# bolid-mcu.net
KiCad netlist of a schematic drawn in Altium Designer
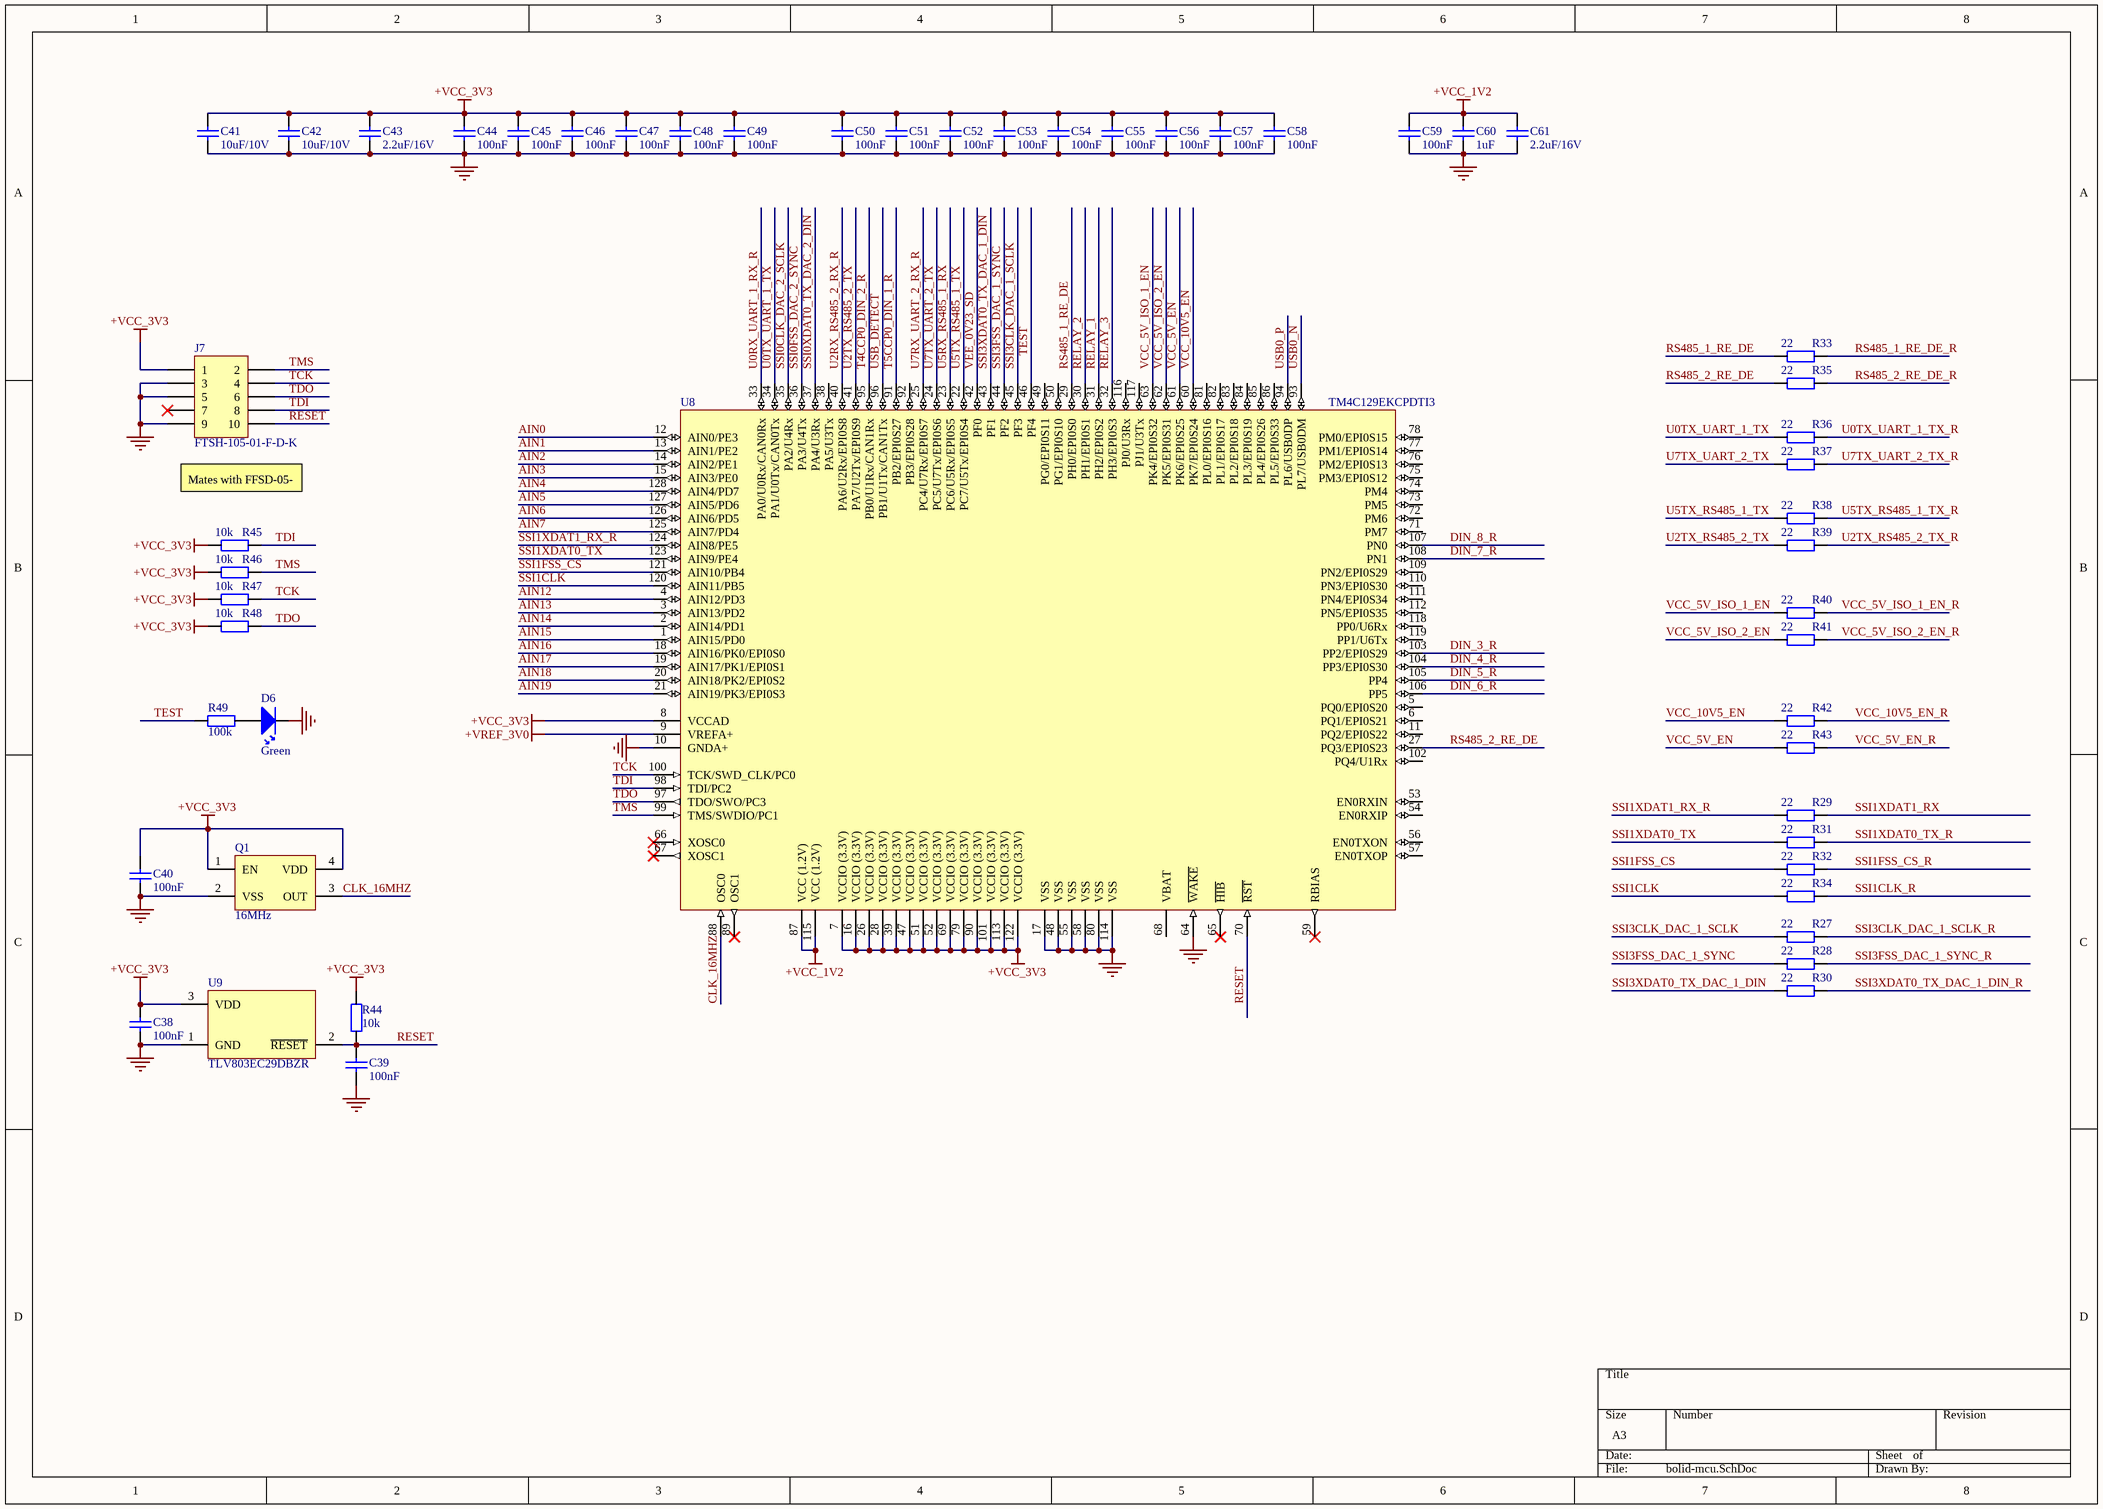
[diagram p0: bolid-mcu.SchDoc]

(export (version "E")
  (design (tool "Eeschema 10.0.6"))
  (components
    (comp (ref "C38")
      (value "GRM155R71H104KE14D")
      (footprint "C0402-CAPC100X50X55L22 - Tayio Yuden TDK")
      (description "MLCC 0402 (1005) 100nF 10% 50V X7R")
      (fields
        (field (name "MANUFACTURER") "Murata Electronics")
        (field (name "TOLERANCE") "10 %")
        (field (name "VALUE DISPLAYED") "100nF")
      )
      (libsource (lib "capacitors2") (part "GRM155R71H104KE14D"))
    )
    (comp (ref "C39")
      (value "GRM155R71H104KE14D")
      (footprint "C0402-CAPC100X50X55L22 - Tayio Yuden TDK")
      (description "MLCC 0402 (1005) 100nF 10% 50V X7R")
      (fields
        (field (name "MANUFACTURER") "Murata Electronics")
        (field (name "TOLERANCE") "10 %")
        (field (name "VALUE DISPLAYED") "100nF")
      )
      (libsource (lib "capacitors2") (part "GRM155R71H104KE14D"))
    )
    (comp (ref "C40")
      (value "GRM155R71H104KE14D")
      (footprint "C0402-CAPC100X50X55L22 - Tayio Yuden TDK")
      (description "MLCC 0402 (1005) 100nF 10% 50V X7R")
      (fields
        (field (name "MANUFACTURER") "Murata Electronics")
        (field (name "TOLERANCE") "10 %")
        (field (name "VALUE DISPLAYED") "100nF")
      )
      (libsource (lib "capacitors2") (part "GRM155R71H104KE14D"))
    )
    (comp (ref "C41")
      (value "GRM21BR71A106KA73K")
      (footprint "C0805-CAPC200X125X135L50N - Taiyo YudenN")
      (description "MLCC 0805 (2012) 10uF 10% 10V X7R")
      (fields
        (field (name "MANUFACTURER") "Murata Electronics")
        (field (name "TOLERANCE") "10 %")
        (field (name "VALUE DISPLAYED") "10uF/10V")
      )
      (libsource (lib "capacitors2") (part "GRM21BR71A106KA73K"))
    )
    (comp (ref "C42")
      (value "GRM21BR71A106KA73K")
      (footprint "C0805-CAPC200X125X135L50N - Taiyo YudenN")
      (description "MLCC 0805 (2012) 10uF 10% 10V X7R")
      (fields
        (field (name "MANUFACTURER") "Murata Electronics")
        (field (name "TOLERANCE") "10 %")
        (field (name "VALUE DISPLAYED") "10uF/10V")
      )
      (libsource (lib "capacitors2") (part "GRM21BR71A106KA73K"))
    )
    (comp (ref "C43")
      (value "EMK107BB7225MA-T")
      (footprint "C0603-CAPC162X80X95L35N")
      (description "MLCC 0603 (1608) 2.2uF 20% 16V X7R")
      (fields
        (field (name "MANUFACTURER") "Taiyo Yuden")
        (field (name "TOLERANCE") "20 %")
        (field (name "VALUE DISPLAYED") "2.2uF/16V")
      )
      (libsource (lib "capacitors2") (part "EMK107BB7225MA-T"))
    )
    (comp (ref "C44")
      (value "GRM155R71H104KE14D")
      (footprint "C0402-CAPC100X50X55L22 - Tayio Yuden TDK")
      (description "MLCC 0402 (1005) 100nF 10% 50V X7R")
      (fields
        (field (name "MANUFACTURER") "Murata Electronics")
        (field (name "TOLERANCE") "10 %")
        (field (name "VALUE DISPLAYED") "100nF")
      )
      (libsource (lib "capacitors2") (part "GRM155R71H104KE14D"))
    )
    (comp (ref "C45")
      (value "GRM155R71H104KE14D")
      (footprint "C0402-CAPC100X50X55L22 - Tayio Yuden TDK")
      (description "MLCC 0402 (1005) 100nF 10% 50V X7R")
      (fields
        (field (name "MANUFACTURER") "Murata Electronics")
        (field (name "TOLERANCE") "10 %")
        (field (name "VALUE DISPLAYED") "100nF")
      )
      (libsource (lib "capacitors2") (part "GRM155R71H104KE14D"))
    )
    (comp (ref "C46")
      (value "GRM155R71H104KE14D")
      (footprint "C0402-CAPC100X50X55L22 - Tayio Yuden TDK")
      (description "MLCC 0402 (1005) 100nF 10% 50V X7R")
      (fields
        (field (name "MANUFACTURER") "Murata Electronics")
        (field (name "TOLERANCE") "10 %")
        (field (name "VALUE DISPLAYED") "100nF")
      )
      (libsource (lib "capacitors2") (part "GRM155R71H104KE14D"))
    )
    (comp (ref "C47")
      (value "GRM155R71H104KE14D")
      (footprint "C0402-CAPC100X50X55L22 - Tayio Yuden TDK")
      (description "MLCC 0402 (1005) 100nF 10% 50V X7R")
      (fields
        (field (name "MANUFACTURER") "Murata Electronics")
        (field (name "TOLERANCE") "10 %")
        (field (name "VALUE DISPLAYED") "100nF")
      )
      (libsource (lib "capacitors2") (part "GRM155R71H104KE14D"))
    )
    (comp (ref "C48")
      (value "GRM155R71H104KE14D")
      (footprint "C0402-CAPC100X50X55L22 - Tayio Yuden TDK")
      (description "MLCC 0402 (1005) 100nF 10% 50V X7R")
      (fields
        (field (name "MANUFACTURER") "Murata Electronics")
        (field (name "TOLERANCE") "10 %")
        (field (name "VALUE DISPLAYED") "100nF")
      )
      (libsource (lib "capacitors2") (part "GRM155R71H104KE14D"))
    )
    (comp (ref "C49")
      (value "GRM155R71H104KE14D")
      (footprint "C0402-CAPC100X50X55L22 - Tayio Yuden TDK")
      (description "MLCC 0402 (1005) 100nF 10% 50V X7R")
      (fields
        (field (name "MANUFACTURER") "Murata Electronics")
        (field (name "TOLERANCE") "10 %")
        (field (name "VALUE DISPLAYED") "100nF")
      )
      (libsource (lib "capacitors2") (part "GRM155R71H104KE14D"))
    )
    (comp (ref "C50")
      (value "GRM155R71H104KE14D")
      (footprint "C0402-CAPC100X50X55L22 - Tayio Yuden TDK")
      (description "MLCC 0402 (1005) 100nF 10% 50V X7R")
      (fields
        (field (name "MANUFACTURER") "Murata Electronics")
        (field (name "TOLERANCE") "10 %")
        (field (name "VALUE DISPLAYED") "100nF")
      )
      (libsource (lib "capacitors2") (part "GRM155R71H104KE14D"))
    )
    (comp (ref "C51")
      (value "GRM155R71H104KE14D")
      (footprint "C0402-CAPC100X50X55L22 - Tayio Yuden TDK")
      (description "MLCC 0402 (1005) 100nF 10% 50V X7R")
      (fields
        (field (name "MANUFACTURER") "Murata Electronics")
        (field (name "TOLERANCE") "10 %")
        (field (name "VALUE DISPLAYED") "100nF")
      )
      (libsource (lib "capacitors2") (part "GRM155R71H104KE14D"))
    )
    (comp (ref "C52")
      (value "GRM155R71H104KE14D")
      (footprint "C0402-CAPC100X50X55L22 - Tayio Yuden TDK")
      (description "MLCC 0402 (1005) 100nF 10% 50V X7R")
      (fields
        (field (name "MANUFACTURER") "Murata Electronics")
        (field (name "TOLERANCE") "10 %")
        (field (name "VALUE DISPLAYED") "100nF")
      )
      (libsource (lib "capacitors2") (part "GRM155R71H104KE14D"))
    )
    (comp (ref "C53")
      (value "GRM155R71H104KE14D")
      (footprint "C0402-CAPC100X50X55L22 - Tayio Yuden TDK")
      (description "MLCC 0402 (1005) 100nF 10% 50V X7R")
      (fields
        (field (name "MANUFACTURER") "Murata Electronics")
        (field (name "TOLERANCE") "10 %")
        (field (name "VALUE DISPLAYED") "100nF")
      )
      (libsource (lib "capacitors2") (part "GRM155R71H104KE14D"))
    )
    (comp (ref "C54")
      (value "GRM155R71H104KE14D")
      (footprint "C0402-CAPC100X50X55L22 - Tayio Yuden TDK")
      (description "MLCC 0402 (1005) 100nF 10% 50V X7R")
      (fields
        (field (name "MANUFACTURER") "Murata Electronics")
        (field (name "TOLERANCE") "10 %")
        (field (name "VALUE DISPLAYED") "100nF")
      )
      (libsource (lib "capacitors2") (part "GRM155R71H104KE14D"))
    )
    (comp (ref "C55")
      (value "GRM155R71H104KE14D")
      (footprint "C0402-CAPC100X50X55L22 - Tayio Yuden TDK")
      (description "MLCC 0402 (1005) 100nF 10% 50V X7R")
      (fields
        (field (name "MANUFACTURER") "Murata Electronics")
        (field (name "TOLERANCE") "10 %")
        (field (name "VALUE DISPLAYED") "100nF")
      )
      (libsource (lib "capacitors2") (part "GRM155R71H104KE14D"))
    )
    (comp (ref "C56")
      (value "GRM155R71H104KE14D")
      (footprint "C0402-CAPC100X50X55L22 - Tayio Yuden TDK")
      (description "MLCC 0402 (1005) 100nF 10% 50V X7R")
      (fields
        (field (name "MANUFACTURER") "Murata Electronics")
        (field (name "TOLERANCE") "10 %")
        (field (name "VALUE DISPLAYED") "100nF")
      )
      (libsource (lib "capacitors2") (part "GRM155R71H104KE14D"))
    )
    (comp (ref "C57")
      (value "GRM155R71H104KE14D")
      (footprint "C0402-CAPC100X50X55L22 - Tayio Yuden TDK")
      (description "MLCC 0402 (1005) 100nF 10% 50V X7R")
      (fields
        (field (name "MANUFACTURER") "Murata Electronics")
        (field (name "TOLERANCE") "10 %")
        (field (name "VALUE DISPLAYED") "100nF")
      )
      (libsource (lib "capacitors2") (part "GRM155R71H104KE14D"))
    )
    (comp (ref "C58")
      (value "GRM155R71H104KE14D")
      (footprint "C0402-CAPC100X50X55L22 - Tayio Yuden TDK")
      (description "MLCC 0402 (1005) 100nF 10% 50V X7R")
      (fields
        (field (name "MANUFACTURER") "Murata Electronics")
        (field (name "TOLERANCE") "10 %")
        (field (name "VALUE DISPLAYED") "100nF")
      )
      (libsource (lib "capacitors2") (part "GRM155R71H104KE14D"))
    )
    (comp (ref "C59")
      (value "GRM155R71H104KE14D")
      (footprint "C0402-CAPC100X50X55L22 - Tayio Yuden TDK")
      (description "MLCC 0402 (1005) 100nF 10% 50V X7R")
      (fields
        (field (name "MANUFACTURER") "Murata Electronics")
        (field (name "TOLERANCE") "10 %")
        (field (name "VALUE DISPLAYED") "100nF")
      )
      (libsource (lib "capacitors2") (part "GRM155R71H104KE14D"))
    )
    (comp (ref "C60")
      (value "UMK107AB7105KA-T")
      (footprint "C0603-CAPC162X80X95L35N")
      (description "MLCC 0603 (1608) 1uF 10% 50V X7R")
      (fields
        (field (name "MANUFACTURER") "Taiyo Yuden")
        (field (name "TOLERANCE") "10 %")
        (field (name "VALUE DISPLAYED") "1uF")
      )
      (libsource (lib "capacitors2") (part "UMK107AB7105KA-T"))
    )
    (comp (ref "C61")
      (value "EMK107BB7225MA-T")
      (footprint "C0603-CAPC162X80X95L35N")
      (description "MLCC 0603 (1608) 2.2uF 20% 16V X7R")
      (fields
        (field (name "MANUFACTURER") "Taiyo Yuden")
        (field (name "TOLERANCE") "20 %")
        (field (name "VALUE DISPLAYED") "2.2uF/16V")
      )
      (libsource (lib "capacitors2") (part "EMK107BB7225MA-T"))
    )
    (comp (ref "D6")
      (value "150060GS75000")
      (footprint "D0603 DIONC166X84X36L42N Littelfuse")
      (description "LED 0603 (1608) Green")
      (fields (field (name "MANUFACTURER") "Wurth Elektronik") (field (name "ILLUMINATION COLOR") "Green"))
      (libsource (lib "semiconductors2") (part "150060GS75000"))
    )
    (comp (ref "J7")
      (value "FTSH-105-01-F-D-K")
      (footprint "SAMTEC-FTSH-105-01-F-D-K")
      (description "Conn Unshrouded Header HDR 10 POS 1.27mm Solder ST Top Entry Thru-Hole Tube")
      (fields (field (name "MANUFACTURER") "Samtec"))
      (libsource (lib "connectors2") (part "FTSH-105-01-F-D-K"))
    )
    (comp (ref "Q1")
      (value "16MHz")
      (footprint "ECS ECS-2520S OSCCC250X200X100L67X77")
      (description "Oscillator XO 16MHz ±25ppm 15pF CMOS 55% 1.8V/2.5V/3.3V 4-Pin Mini-CSMD T/R")
      (fields
        (field (name "MANUFACTURER") "ECS International")
        (field (name "MANUFACTURER PART NUMBER") "ECS-2520MVLC-160-CN-TR")
      )
      (libsource (lib "misc2") (part "ECS-2520MVLC-160-CN-TR"))
    )
    (comp (ref "R27")
      (value "22")
      (footprint "R0402-RESC100X50X40L22N")
      (description "RES 0402 (1005) 22.0 ohm 1% 0.0625W 50V Thick Film")
      (fields
        (field (name "MANUFACTURER") "Yageo")
        (field (name "MANUFACTURER PART NUMBER") "RC0402FR-1322RL")
      )
      (libsource (lib "resistors2") (part "RC0402FR-1322RL"))
    )
    (comp (ref "R28")
      (value "22")
      (footprint "R0402-RESC100X50X40L22N")
      (description "RES 0402 (1005) 22.0 ohm 1% 0.0625W 50V Thick Film")
      (fields
        (field (name "MANUFACTURER") "Yageo")
        (field (name "MANUFACTURER PART NUMBER") "RC0402FR-1322RL")
      )
      (libsource (lib "resistors2") (part "RC0402FR-1322RL"))
    )
    (comp (ref "R29")
      (value "22")
      (footprint "R0402-RESC100X50X40L22N")
      (description "RES 0402 (1005) 22.0 ohm 1% 0.0625W 50V Thick Film")
      (fields
        (field (name "MANUFACTURER") "Yageo")
        (field (name "MANUFACTURER PART NUMBER") "RC0402FR-1322RL")
      )
      (libsource (lib "resistors2") (part "RC0402FR-1322RL"))
    )
    (comp (ref "R30")
      (value "22")
      (footprint "R0402-RESC100X50X40L22N")
      (description "RES 0402 (1005) 22.0 ohm 1% 0.0625W 50V Thick Film")
      (fields
        (field (name "MANUFACTURER") "Yageo")
        (field (name "MANUFACTURER PART NUMBER") "RC0402FR-1322RL")
      )
      (libsource (lib "resistors2") (part "RC0402FR-1322RL"))
    )
    (comp (ref "R31")
      (value "22")
      (footprint "R0402-RESC100X50X40L22N")
      (description "RES 0402 (1005) 22.0 ohm 1% 0.0625W 50V Thick Film")
      (fields
        (field (name "MANUFACTURER") "Yageo")
        (field (name "MANUFACTURER PART NUMBER") "RC0402FR-1322RL")
      )
      (libsource (lib "resistors2") (part "RC0402FR-1322RL"))
    )
    (comp (ref "R32")
      (value "22")
      (footprint "R0402-RESC100X50X40L22N")
      (description "RES 0402 (1005) 22.0 ohm 1% 0.0625W 50V Thick Film")
      (fields
        (field (name "MANUFACTURER") "Yageo")
        (field (name "MANUFACTURER PART NUMBER") "RC0402FR-1322RL")
      )
      (libsource (lib "resistors2") (part "RC0402FR-1322RL"))
    )
    (comp (ref "R33")
      (value "22")
      (footprint "R0402-RESC100X50X40L22N")
      (description "RES 0402 (1005) 22.0 ohm 1% 0.0625W 50V Thick Film")
      (fields
        (field (name "MANUFACTURER") "Yageo")
        (field (name "MANUFACTURER PART NUMBER") "RC0402FR-1322RL")
      )
      (libsource (lib "resistors2") (part "RC0402FR-1322RL"))
    )
    (comp (ref "R34")
      (value "22")
      (footprint "R0402-RESC100X50X40L22N")
      (description "RES 0402 (1005) 22.0 ohm 1% 0.0625W 50V Thick Film")
      (fields
        (field (name "MANUFACTURER") "Yageo")
        (field (name "MANUFACTURER PART NUMBER") "RC0402FR-1322RL")
      )
      (libsource (lib "resistors2") (part "RC0402FR-1322RL"))
    )
    (comp (ref "R35")
      (value "22")
      (footprint "R0402-RESC100X50X40L22N")
      (description "RES 0402 (1005) 22.0 ohm 1% 0.0625W 50V Thick Film")
      (fields
        (field (name "MANUFACTURER") "Yageo")
        (field (name "MANUFACTURER PART NUMBER") "RC0402FR-1322RL")
      )
      (libsource (lib "resistors2") (part "RC0402FR-1322RL"))
    )
    (comp (ref "R36")
      (value "22")
      (footprint "R0402-RESC100X50X40L22N")
      (description "RES 0402 (1005) 22.0 ohm 1% 0.0625W 50V Thick Film")
      (fields
        (field (name "MANUFACTURER") "Yageo")
        (field (name "MANUFACTURER PART NUMBER") "RC0402FR-1322RL")
      )
      (libsource (lib "resistors2") (part "RC0402FR-1322RL"))
    )
    (comp (ref "R37")
      (value "22")
      (footprint "R0402-RESC100X50X40L22N")
      (description "RES 0402 (1005) 22.0 ohm 1% 0.0625W 50V Thick Film")
      (fields
        (field (name "MANUFACTURER") "Yageo")
        (field (name "MANUFACTURER PART NUMBER") "RC0402FR-1322RL")
      )
      (libsource (lib "resistors2") (part "RC0402FR-1322RL"))
    )
    (comp (ref "R38")
      (value "22")
      (footprint "R0402-RESC100X50X40L22N")
      (description "RES 0402 (1005) 22.0 ohm 1% 0.0625W 50V Thick Film")
      (fields
        (field (name "MANUFACTURER") "Yageo")
        (field (name "MANUFACTURER PART NUMBER") "RC0402FR-1322RL")
      )
      (libsource (lib "resistors2") (part "RC0402FR-1322RL"))
    )
    (comp (ref "R39")
      (value "22")
      (footprint "R0402-RESC100X50X40L22N")
      (description "RES 0402 (1005) 22.0 ohm 1% 0.0625W 50V Thick Film")
      (fields
        (field (name "MANUFACTURER") "Yageo")
        (field (name "MANUFACTURER PART NUMBER") "RC0402FR-1322RL")
      )
      (libsource (lib "resistors2") (part "RC0402FR-1322RL"))
    )
    (comp (ref "R40")
      (value "22")
      (footprint "R0402-RESC100X50X40L22N")
      (description "RES 0402 (1005) 22.0 ohm 1% 0.0625W 50V Thick Film")
      (fields
        (field (name "MANUFACTURER") "Yageo")
        (field (name "MANUFACTURER PART NUMBER") "RC0402FR-1322RL")
      )
      (libsource (lib "resistors2") (part "RC0402FR-1322RL"))
    )
    (comp (ref "R41")
      (value "22")
      (footprint "R0402-RESC100X50X40L22N")
      (description "RES 0402 (1005) 22.0 ohm 1% 0.0625W 50V Thick Film")
      (fields
        (field (name "MANUFACTURER") "Yageo")
        (field (name "MANUFACTURER PART NUMBER") "RC0402FR-1322RL")
      )
      (libsource (lib "resistors2") (part "RC0402FR-1322RL"))
    )
    (comp (ref "R42")
      (value "22")
      (footprint "R0402-RESC100X50X40L22N")
      (description "RES 0402 (1005) 22.0 ohm 1% 0.0625W 50V Thick Film")
      (fields
        (field (name "MANUFACTURER") "Yageo")
        (field (name "MANUFACTURER PART NUMBER") "RC0402FR-1322RL")
      )
      (libsource (lib "resistors2") (part "RC0402FR-1322RL"))
    )
    (comp (ref "R43")
      (value "22")
      (footprint "R0402-RESC100X50X40L22N")
      (description "RES 0402 (1005) 22.0 ohm 1% 0.0625W 50V Thick Film")
      (fields
        (field (name "MANUFACTURER") "Yageo")
        (field (name "MANUFACTURER PART NUMBER") "RC0402FR-1322RL")
      )
      (libsource (lib "resistors2") (part "RC0402FR-1322RL"))
    )
    (comp (ref "R44")
      (value "10k")
      (footprint "R0402-RESC100X50X40L22N")
      (description "RES 0402 (1005) 10.0k 1% 0.0625W 50V Thick Film")
      (fields
        (field (name "MANUFACTURER") "Yageo")
        (field (name "MANUFACTURER PART NUMBER") "RC0402FR-0710KL")
      )
      (libsource (lib "resistors2") (part "RC0402FR-0710KL"))
    )
    (comp (ref "R45")
      (value "10k")
      (footprint "R0402-RESC100X50X40L22N")
      (description "RES 0402 (1005) 10.0k 1% 0.0625W 50V Thick Film")
      (fields
        (field (name "MANUFACTURER") "Yageo")
        (field (name "MANUFACTURER PART NUMBER") "RC0402FR-0710KL")
      )
      (libsource (lib "") (part "RC0402FR-0710KL_1"))
    )
    (comp (ref "R46")
      (value "10k")
      (footprint "R0402-RESC100X50X40L22N")
      (description "RES 0402 (1005) 10.0k 1% 0.0625W 50V Thick Film")
      (fields
        (field (name "MANUFACTURER") "Yageo")
        (field (name "MANUFACTURER PART NUMBER") "RC0402FR-0710KL")
      )
      (libsource (lib "") (part "RC0402FR-0710KL_1"))
    )
    (comp (ref "R47")
      (value "10k")
      (footprint "R0402-RESC100X50X40L22N")
      (description "RES 0402 (1005) 10.0k 1% 0.0625W 50V Thick Film")
      (fields
        (field (name "MANUFACTURER") "Yageo")
        (field (name "MANUFACTURER PART NUMBER") "RC0402FR-0710KL")
      )
      (libsource (lib "") (part "RC0402FR-0710KL_1"))
    )
    (comp (ref "R48")
      (value "10k")
      (footprint "R0402-RESC100X50X40L22N")
      (description "RES 0402 (1005) 10.0k 1% 0.0625W 50V Thick Film")
      (fields
        (field (name "MANUFACTURER") "Yageo")
        (field (name "MANUFACTURER PART NUMBER") "RC0402FR-0710KL")
      )
      (libsource (lib "") (part "RC0402FR-0710KL_1"))
    )
    (comp (ref "R49")
      (value "100k")
      (footprint "R0402-RESC100X50X40L22N")
      (description "RES 0402 (1005) 100.0k 1% 0.0625W 50V Thick Film")
      (fields
        (field (name "MANUFACTURER") "Yageo")
        (field (name "MANUFACTURER PART NUMBER") "RC0402FR-07100KL")
      )
      (libsource (lib "resistors2") (part "RC0402FR-07100KL"))
    )
    (comp (ref "U8")
      (value "TM4C129EKCPDTI3")
      (footprint "TI TQFP128 PDT S-PQFP-G128 QFP128P40_1600X1600X105L60X18NN")
      (description "ARM Microcontrollers - MCU Tiva C Series Microcontroller")
      (fields (field (name "MANUFACTURER") "Texas Instruments"))
      (libsource (lib "ics2") (part "TM4C129EKCPDTI3"))
    )
    (comp (ref "U9")
      (value "TLV803EC29DBZR")
      (footprint "TI SOT23 DBZ0003A SOT23-3P95_237X112L40X40N")
      (fields (field (name "MANUFACTURER") "Texas Instruments"))
      (libsource (lib "ics2") (part "TLV803EC29DBZR"))
    )
  )
  (nets
    (net (code "1") (name "+VCC_1V2") (class "Default")
      (node (ref "C59") (pin "2") (pinfunction "2_2") (pintype "passive"))
      (node (ref "C60") (pin "2") (pinfunction "2_2") (pintype "passive"))
      (node (ref "C61") (pin "2") (pinfunction "2_2") (pintype "passive"))
      (node (ref "U8") (pin "115") (pinfunction "VCC_(1.2V)_115") (pintype "power_in"))
      (node (ref "U8") (pin "87") (pinfunction "VCC_(1.2V)_87") (pintype "power_in"))
    )
    (net (code "2") (name "+VCC_3V3") (class "Default")
      (node (ref "C38") (pin "2") (pinfunction "2_2") (pintype "passive"))
      (node (ref "C40") (pin "2") (pinfunction "2_2") (pintype "passive"))
      (node (ref "C41") (pin "2") (pinfunction "2_2") (pintype "passive"))
      (node (ref "C42") (pin "2") (pinfunction "2_2") (pintype "passive"))
      (node (ref "C43") (pin "2") (pinfunction "2_2") (pintype "passive"))
      (node (ref "C44") (pin "2") (pinfunction "2_2") (pintype "passive"))
      (node (ref "C45") (pin "2") (pinfunction "2_2") (pintype "passive"))
      (node (ref "C46") (pin "2") (pinfunction "2_2") (pintype "passive"))
      (node (ref "C47") (pin "2") (pinfunction "2_2") (pintype "passive"))
      (node (ref "C48") (pin "2") (pinfunction "2_2") (pintype "passive"))
      (node (ref "C49") (pin "2") (pinfunction "2_2") (pintype "passive"))
      (node (ref "C50") (pin "2") (pinfunction "2_2") (pintype "passive"))
      (node (ref "C51") (pin "2") (pinfunction "2_2") (pintype "passive"))
      (node (ref "C52") (pin "2") (pinfunction "2_2") (pintype "passive"))
      (node (ref "C53") (pin "2") (pinfunction "2_2") (pintype "passive"))
      (node (ref "C54") (pin "2") (pinfunction "2_2") (pintype "passive"))
      (node (ref "C55") (pin "2") (pinfunction "2_2") (pintype "passive"))
      (node (ref "C56") (pin "2") (pinfunction "2_2") (pintype "passive"))
      (node (ref "C57") (pin "2") (pinfunction "2_2") (pintype "passive"))
      (node (ref "C58") (pin "2") (pinfunction "2_2") (pintype "passive"))
      (node (ref "J7") (pin "1") (pinfunction "1_1") (pintype "passive"))
      (node (ref "Q1") (pin "1") (pinfunction "EN_1") (pintype "passive"))
      (node (ref "Q1") (pin "4") (pinfunction "VDD_4") (pintype "passive"))
      (node (ref "R44") (pin "1") (pinfunction "1_1") (pintype "passive"))
      (node (ref "R45") (pin "2") (pinfunction "2_2") (pintype "passive"))
      (node (ref "R46") (pin "2") (pinfunction "2_2") (pintype "passive"))
      (node (ref "R47") (pin "2") (pinfunction "2_2") (pintype "passive"))
      (node (ref "R48") (pin "2") (pinfunction "2_2") (pintype "passive"))
      (node (ref "U8") (pin "101") (pinfunction "VCCIO_(3.3V)_101") (pintype "power_in"))
      (node (ref "U8") (pin "113") (pinfunction "VCCIO_(3.3V)_113") (pintype "power_in"))
      (node (ref "U8") (pin "122") (pinfunction "VCCIO_(3.3V)_122") (pintype "power_in"))
      (node (ref "U8") (pin "16") (pinfunction "VCCIO_(3.3V)_16") (pintype "power_in"))
      (node (ref "U8") (pin "26") (pinfunction "VCCIO_(3.3V)_26") (pintype "power_in"))
      (node (ref "U8") (pin "28") (pinfunction "VCCIO_(3.3V)_28") (pintype "power_in"))
      (node (ref "U8") (pin "39") (pinfunction "VCCIO_(3.3V)_39") (pintype "power_in"))
      (node (ref "U8") (pin "47") (pinfunction "VCCIO_(3.3V)_47") (pintype "power_in"))
      (node (ref "U8") (pin "51") (pinfunction "VCCIO_(3.3V)_51") (pintype "power_in"))
      (node (ref "U8") (pin "52") (pinfunction "VCCIO_(3.3V)_52") (pintype "power_in"))
      (node (ref "U8") (pin "69") (pinfunction "VCCIO_(3.3V)_69") (pintype "power_in"))
      (node (ref "U8") (pin "7") (pinfunction "VCCIO_(3.3V)_7") (pintype "power_in"))
      (node (ref "U8") (pin "79") (pinfunction "VCCIO_(3.3V)_79") (pintype "power_in"))
      (node (ref "U8") (pin "8") (pinfunction "VCCAD_8") (pintype "power_in"))
      (node (ref "U8") (pin "90") (pinfunction "VCCIO_(3.3V)_90") (pintype "power_in"))
      (node (ref "U9") (pin "3") (pinfunction "VDD_3") (pintype "passive"))
    )
    (net (code "3") (name "+VREF_3V0") (class "Default")
      (node (ref "U8") (pin "9") (pinfunction "VREFA+_9") (pintype "power_in"))
    )
    (net (code "4") (name "/AIN0") (class "Default")
      (node (ref "U8") (pin "12") (pinfunction "AIN0/PE3_12") (pintype "bidirectional"))
    )
    (net (code "5") (name "/AIN1") (class "Default")
      (node (ref "U8") (pin "13") (pinfunction "AIN1/PE2_13") (pintype "bidirectional"))
    )
    (net (code "6") (name "/AIN2") (class "Default")
      (node (ref "U8") (pin "14") (pinfunction "AIN2/PE1_14") (pintype "bidirectional"))
    )
    (net (code "7") (name "/AIN3") (class "Default")
      (node (ref "U8") (pin "15") (pinfunction "AIN3/PE0_15") (pintype "bidirectional"))
    )
    (net (code "8") (name "/AIN4") (class "Default")
      (node (ref "U8") (pin "128") (pinfunction "AIN4/PD7_128") (pintype "bidirectional"))
    )
    (net (code "9") (name "/AIN5") (class "Default")
      (node (ref "U8") (pin "127") (pinfunction "AIN5/PD6_127") (pintype "bidirectional"))
    )
    (net (code "10") (name "/AIN6") (class "Default")
      (node (ref "U8") (pin "126") (pinfunction "AIN6/PD5_126") (pintype "bidirectional"))
    )
    (net (code "11") (name "/AIN7") (class "Default")
      (node (ref "U8") (pin "125") (pinfunction "AIN7/PD4_125") (pintype "bidirectional"))
    )
    (net (code "12") (name "/AIN12") (class "Default")
      (node (ref "U8") (pin "4") (pinfunction "AIN12/PD3_4") (pintype "bidirectional"))
    )
    (net (code "13") (name "/AIN13") (class "Default")
      (node (ref "U8") (pin "3") (pinfunction "AIN13/PD2_3") (pintype "bidirectional"))
    )
    (net (code "14") (name "/AIN14") (class "Default")
      (node (ref "U8") (pin "2") (pinfunction "AIN14/PD1_2") (pintype "bidirectional"))
    )
    (net (code "15") (name "/AIN15") (class "Default")
      (node (ref "U8") (pin "1") (pinfunction "AIN15/PD0_1") (pintype "bidirectional"))
    )
    (net (code "16") (name "/AIN16") (class "Default")
      (node (ref "U8") (pin "18") (pinfunction "AIN16/PK0/EPI0S0_18") (pintype "bidirectional"))
    )
    (net (code "17") (name "/AIN17") (class "Default")
      (node (ref "U8") (pin "19") (pinfunction "AIN17/PK1/EPI0S1_19") (pintype "bidirectional"))
    )
    (net (code "18") (name "/AIN18") (class "Default")
      (node (ref "U8") (pin "20") (pinfunction "AIN18/PK2/EPI0S2_20") (pintype "bidirectional"))
    )
    (net (code "19") (name "/AIN19") (class "Default")
      (node (ref "U8") (pin "21") (pinfunction "AIN19/PK3/EPI0S3_21") (pintype "bidirectional"))
    )
    (net (code "20") (name "/CLK_16MHZ") (class "Default")
      (node (ref "Q1") (pin "3") (pinfunction "OUT_3") (pintype "passive"))
      (node (ref "U8") (pin "88") (pinfunction "OSC0_88") (pintype "input"))
    )
    (net (code "21") (name "/DIN_3_R") (class "Default")
      (node (ref "U8") (pin "103") (pinfunction "PP2/EPI0S29_103") (pintype "bidirectional"))
    )
    (net (code "22") (name "/DIN_4_R") (class "Default")
      (node (ref "U8") (pin "104") (pinfunction "PP3/EPI0S30_104") (pintype "bidirectional"))
    )
    (net (code "23") (name "/DIN_5_R") (class "Default")
      (node (ref "U8") (pin "105") (pinfunction "PP4_105") (pintype "bidirectional"))
    )
    (net (code "24") (name "/DIN_6_R") (class "Default")
      (node (ref "U8") (pin "106") (pinfunction "PP5_106") (pintype "bidirectional"))
    )
    (net (code "25") (name "/DIN_7_R") (class "Default")
      (node (ref "U8") (pin "108") (pinfunction "PN1_108") (pintype "bidirectional"))
    )
    (net (code "26") (name "/DIN_8_R") (class "Default")
      (node (ref "U8") (pin "107") (pinfunction "PN0_107") (pintype "bidirectional"))
    )
    (net (code "27") (name "/RELAY_1") (class "Default")
      (node (ref "U8") (pin "31") (pinfunction "PH2/EPI0S2_31") (pintype "bidirectional"))
    )
    (net (code "28") (name "/RELAY_2") (class "Default")
      (node (ref "U8") (pin "30") (pinfunction "PH1/EPI0S1_30") (pintype "bidirectional"))
    )
    (net (code "29") (name "/RELAY_3") (class "Default")
      (node (ref "U8") (pin "32") (pinfunction "PH3/EPI0S3_32") (pintype "bidirectional"))
    )
    (net (code "30") (name "/RESET") (class "Default")
      (node (ref "C39") (pin "2") (pinfunction "2_2") (pintype "passive"))
      (node (ref "J7") (pin "10") (pinfunction "10_10") (pintype "passive"))
      (node (ref "R44") (pin "2") (pinfunction "2_2") (pintype "passive"))
      (node (ref "U8") (pin "70") (pinfunction "~{RST}_70") (pintype "input"))
      (node (ref "U9") (pin "2") (pinfunction "~{RESET}_2") (pintype "passive"))
    )
    (net (code "31") (name "/RS485_1_RE_DE") (class "Default")
      (node (ref "R33") (pin "1") (pinfunction "1_1") (pintype "passive"))
      (node (ref "U8") (pin "29") (pinfunction "PH0/EPI0S0_29") (pintype "bidirectional"))
    )
    (net (code "32") (name "/RS485_1_RE_DE_R") (class "Default")
      (node (ref "R33") (pin "2") (pinfunction "2_2") (pintype "passive"))
    )
    (net (code "33") (name "/RS485_2_RE_DE") (class "Default")
      (node (ref "R35") (pin "1") (pinfunction "1_1") (pintype "passive"))
      (node (ref "U8") (pin "27") (pinfunction "PQ3/EPI0S23_27") (pintype "bidirectional"))
    )
    (net (code "34") (name "/RS485_2_RE_DE_R") (class "Default")
      (node (ref "R35") (pin "2") (pinfunction "2_2") (pintype "passive"))
    )
    (net (code "35") (name "/SSI0CLK_DAC_2_SCLK") (class "Default")
      (node (ref "U8") (pin "35") (pinfunction "PA2/U4Rx_35") (pintype "bidirectional"))
    )
    (net (code "36") (name "/SSI0FSS_DAC_2_SYNC") (class "Default")
      (node (ref "U8") (pin "36") (pinfunction "PA3/U4Tx_36") (pintype "bidirectional"))
    )
    (net (code "37") (name "/SSI0XDAT0_TX_DAC_2_DIN") (class "Default")
      (node (ref "U8") (pin "37") (pinfunction "PA4/U3Rx_37") (pintype "bidirectional"))
    )
    (net (code "38") (name "/SSI1CLK") (class "Default")
      (node (ref "R34") (pin "1") (pinfunction "1_1") (pintype "passive"))
      (node (ref "U8") (pin "120") (pinfunction "AIN11/PB5_120") (pintype "bidirectional"))
    )
    (net (code "39") (name "/SSI1CLK_R") (class "Default")
      (node (ref "R34") (pin "2") (pinfunction "2_2") (pintype "passive"))
    )
    (net (code "40") (name "/SSI1FSS_CS") (class "Default")
      (node (ref "R32") (pin "1") (pinfunction "1_1") (pintype "passive"))
      (node (ref "U8") (pin "121") (pinfunction "AIN10/PB4_121") (pintype "bidirectional"))
    )
    (net (code "41") (name "/SSI1FSS_CS_R") (class "Default")
      (node (ref "R32") (pin "2") (pinfunction "2_2") (pintype "passive"))
    )
    (net (code "42") (name "/SSI1XDAT0_TX") (class "Default")
      (node (ref "R31") (pin "1") (pinfunction "1_1") (pintype "passive"))
      (node (ref "U8") (pin "123") (pinfunction "AIN9/PE4_123") (pintype "bidirectional"))
    )
    (net (code "43") (name "/SSI1XDAT0_TX_R") (class "Default")
      (node (ref "R31") (pin "2") (pinfunction "2_2") (pintype "passive"))
    )
    (net (code "44") (name "/SSI1XDAT1_RX") (class "Default")
      (node (ref "R29") (pin "2") (pinfunction "2_2") (pintype "passive"))
    )
    (net (code "45") (name "/SSI1XDAT1_RX_R") (class "Default")
      (node (ref "R29") (pin "1") (pinfunction "1_1") (pintype "passive"))
      (node (ref "U8") (pin "124") (pinfunction "AIN8/PE5_124") (pintype "bidirectional"))
    )
    (net (code "46") (name "/SSI3CLK_DAC_1_SCLK") (class "Default")
      (node (ref "R27") (pin "1") (pinfunction "1_1") (pintype "passive"))
      (node (ref "U8") (pin "45") (pinfunction "PF3_45") (pintype "bidirectional"))
    )
    (net (code "47") (name "/SSI3CLK_DAC_1_SCLK_R") (class "Default")
      (node (ref "R27") (pin "2") (pinfunction "2_2") (pintype "passive"))
    )
    (net (code "48") (name "/SSI3FSS_DAC_1_SYNC") (class "Default")
      (node (ref "R28") (pin "1") (pinfunction "1_1") (pintype "passive"))
      (node (ref "U8") (pin "44") (pinfunction "PF2_44") (pintype "bidirectional"))
    )
    (net (code "49") (name "/SSI3FSS_DAC_1_SYNC_R") (class "Default")
      (node (ref "R28") (pin "2") (pinfunction "2_2") (pintype "passive"))
    )
    (net (code "50") (name "/SSI3XDAT0_TX_DAC_1_DIN") (class "Default")
      (node (ref "R30") (pin "1") (pinfunction "1_1") (pintype "passive"))
      (node (ref "U8") (pin "43") (pinfunction "PF1_43") (pintype "bidirectional"))
    )
    (net (code "51") (name "/SSI3XDAT0_TX_DAC_1_DIN_R") (class "Default")
      (node (ref "R30") (pin "2") (pinfunction "2_2") (pintype "passive"))
    )
    (net (code "52") (name "/T4CCP0_DIN_2_R") (class "Default")
      (node (ref "U8") (pin "95") (pinfunction "PB0/U1Rx/CAN1Rx_95") (pintype "bidirectional"))
    )
    (net (code "53") (name "/T5CCP0_DIN_1_R") (class "Default")
      (node (ref "U8") (pin "91") (pinfunction "PB2/EPI0S27_91") (pintype "bidirectional"))
    )
    (net (code "54") (name "/TCK") (class "Default")
      (node (ref "J7") (pin "4") (pinfunction "4_4") (pintype "passive"))
      (node (ref "R47") (pin "1") (pinfunction "1_1") (pintype "passive"))
      (node (ref "U8") (pin "100") (pinfunction "TCK/SWD_CLK/PC0_100") (pintype "input"))
    )
    (net (code "55") (name "/TDI") (class "Default")
      (node (ref "J7") (pin "8") (pinfunction "8_8") (pintype "passive"))
      (node (ref "R45") (pin "1") (pinfunction "1_1") (pintype "passive"))
      (node (ref "U8") (pin "98") (pinfunction "TDI/PC2_98") (pintype "input"))
    )
    (net (code "56") (name "/TDO") (class "Default")
      (node (ref "J7") (pin "6") (pinfunction "6_6") (pintype "passive"))
      (node (ref "R48") (pin "1") (pinfunction "1_1") (pintype "passive"))
      (node (ref "U8") (pin "97") (pinfunction "TDO/SWO/PC3_97") (pintype "output"))
    )
    (net (code "57") (name "/TEST") (class "Default")
      (node (ref "R49") (pin "2") (pinfunction "2_2") (pintype "passive"))
      (node (ref "U8") (pin "46") (pinfunction "PF4_46") (pintype "bidirectional"))
    )
    (net (code "58") (name "/TMS") (class "Default")
      (node (ref "J7") (pin "2") (pinfunction "2_2") (pintype "passive"))
      (node (ref "R46") (pin "1") (pinfunction "1_1") (pintype "passive"))
      (node (ref "U8") (pin "99") (pinfunction "TMS/SWDIO/PC1_99") (pintype "input"))
    )
    (net (code "59") (name "/U0RX_UART_1_RX_R") (class "Default")
      (node (ref "U8") (pin "33") (pinfunction "PA0/U0Rx/CAN0Rx_33") (pintype "bidirectional"))
    )
    (net (code "60") (name "/U0TX_UART_1_TX") (class "Default")
      (node (ref "R36") (pin "1") (pinfunction "1_1") (pintype "passive"))
      (node (ref "U8") (pin "34") (pinfunction "PA1/U0Tx/CAN0Tx_34") (pintype "bidirectional"))
    )
    (net (code "61") (name "/U0TX_UART_1_TX_R") (class "Default")
      (node (ref "R36") (pin "2") (pinfunction "2_2") (pintype "passive"))
    )
    (net (code "62") (name "/U2RX_RS485_2_RX_R") (class "Default")
      (node (ref "U8") (pin "40") (pinfunction "PA6/U2Rx/EPI0S8_40") (pintype "bidirectional"))
    )
    (net (code "63") (name "/U2TX_RS485_2_TX") (class "Default")
      (node (ref "R39") (pin "1") (pinfunction "1_1") (pintype "passive"))
      (node (ref "U8") (pin "41") (pinfunction "PA7/U2Tx/EPI0S9_41") (pintype "bidirectional"))
    )
    (net (code "64") (name "/U2TX_RS485_2_TX_R") (class "Default")
      (node (ref "R39") (pin "2") (pinfunction "2_2") (pintype "passive"))
    )
    (net (code "65") (name "/U5RX_RS485_1_RX") (class "Default")
      (node (ref "U8") (pin "23") (pinfunction "PC6/U5Rx/EPI0S5_23") (pintype "bidirectional"))
    )
    (net (code "66") (name "/U5TX_RS485_1_TX") (class "Default")
      (node (ref "R38") (pin "1") (pinfunction "1_1") (pintype "passive"))
      (node (ref "U8") (pin "22") (pinfunction "PC7/U5Tx/EPI0S4_22") (pintype "bidirectional"))
    )
    (net (code "67") (name "/U5TX_RS485_1_TX_R") (class "Default")
      (node (ref "R38") (pin "2") (pinfunction "2_2") (pintype "passive"))
    )
    (net (code "68") (name "/U7RX_UART_2_RX_R") (class "Default")
      (node (ref "U8") (pin "25") (pinfunction "PC4/U7Rx/EPI0S7_25") (pintype "bidirectional"))
    )
    (net (code "69") (name "/U7TX_UART_2_TX") (class "Default")
      (node (ref "R37") (pin "1") (pinfunction "1_1") (pintype "passive"))
      (node (ref "U8") (pin "24") (pinfunction "PC5/U7Tx/EPI0S6_24") (pintype "bidirectional"))
    )
    (net (code "70") (name "/U7TX_UART_2_TX_R") (class "Default")
      (node (ref "R37") (pin "2") (pinfunction "2_2") (pintype "passive"))
    )
    (net (code "71") (name "/USB0_N") (class "Default")
      (node (ref "U8") (pin "93") (pinfunction "PL7/USB0DM_93") (pintype "bidirectional"))
    )
    (net (code "72") (name "/USB0_P") (class "Default")
      (node (ref "U8") (pin "94") (pinfunction "PL6/USB0DP_94") (pintype "bidirectional"))
    )
    (net (code "73") (name "/USB_DETECT") (class "Default")
      (node (ref "U8") (pin "96") (pinfunction "PB1/U1Tx/CAN1Tx_96") (pintype "bidirectional"))
    )
    (net (code "74") (name "/VCC_5V_EN") (class "Default")
      (node (ref "R43") (pin "1") (pinfunction "1_1") (pintype "passive"))
      (node (ref "U8") (pin "61") (pinfunction "PK6/EPI0S25_61") (pintype "bidirectional"))
    )
    (net (code "75") (name "/VCC_5V_EN_R") (class "Default")
      (node (ref "R43") (pin "2") (pinfunction "2_2") (pintype "passive"))
    )
    (net (code "76") (name "/VCC_5V_ISO_1_EN") (class "Default")
      (node (ref "R40") (pin "1") (pinfunction "1_1") (pintype "passive"))
      (node (ref "U8") (pin "63") (pinfunction "PK4/EPI0S32_63") (pintype "bidirectional"))
    )
    (net (code "77") (name "/VCC_5V_ISO_1_EN_R") (class "Default")
      (node (ref "R40") (pin "2") (pinfunction "2_2") (pintype "passive"))
    )
    (net (code "78") (name "/VCC_5V_ISO_2_EN") (class "Default")
      (node (ref "R41") (pin "1") (pinfunction "1_1") (pintype "passive"))
      (node (ref "U8") (pin "62") (pinfunction "PK5/EPI0S31_62") (pintype "bidirectional"))
    )
    (net (code "79") (name "/VCC_5V_ISO_2_EN_R") (class "Default")
      (node (ref "R41") (pin "2") (pinfunction "2_2") (pintype "passive"))
    )
    (net (code "80") (name "/VCC_10V5_EN") (class "Default")
      (node (ref "R42") (pin "1") (pinfunction "1_1") (pintype "passive"))
      (node (ref "U8") (pin "60") (pinfunction "PK7/EPI0S24_60") (pintype "bidirectional"))
    )
    (net (code "81") (name "/VCC_10V5_EN_R") (class "Default")
      (node (ref "R42") (pin "2") (pinfunction "2_2") (pintype "passive"))
    )
    (net (code "82") (name "/VEE_0V23_SD") (class "Default")
      (node (ref "U8") (pin "42") (pinfunction "PF0_42") (pintype "bidirectional"))
    )
    (net (code "83") (name "GND") (class "Default")
      (node (ref "C38") (pin "1") (pinfunction "1_1") (pintype "passive"))
      (node (ref "C39") (pin "1") (pinfunction "1_1") (pintype "passive"))
      (node (ref "C40") (pin "1") (pinfunction "1_1") (pintype "passive"))
      (node (ref "C41") (pin "1") (pinfunction "1_1") (pintype "passive"))
      (node (ref "C42") (pin "1") (pinfunction "1_1") (pintype "passive"))
      (node (ref "C43") (pin "1") (pinfunction "1_1") (pintype "passive"))
      (node (ref "C44") (pin "1") (pinfunction "1_1") (pintype "passive"))
      (node (ref "C45") (pin "1") (pinfunction "1_1") (pintype "passive"))
      (node (ref "C46") (pin "1") (pinfunction "1_1") (pintype "passive"))
      (node (ref "C47") (pin "1") (pinfunction "1_1") (pintype "passive"))
      (node (ref "C48") (pin "1") (pinfunction "1_1") (pintype "passive"))
      (node (ref "C49") (pin "1") (pinfunction "1_1") (pintype "passive"))
      (node (ref "C50") (pin "1") (pinfunction "1_1") (pintype "passive"))
      (node (ref "C51") (pin "1") (pinfunction "1_1") (pintype "passive"))
      (node (ref "C52") (pin "1") (pinfunction "1_1") (pintype "passive"))
      (node (ref "C53") (pin "1") (pinfunction "1_1") (pintype "passive"))
      (node (ref "C54") (pin "1") (pinfunction "1_1") (pintype "passive"))
      (node (ref "C55") (pin "1") (pinfunction "1_1") (pintype "passive"))
      (node (ref "C56") (pin "1") (pinfunction "1_1") (pintype "passive"))
      (node (ref "C57") (pin "1") (pinfunction "1_1") (pintype "passive"))
      (node (ref "C58") (pin "1") (pinfunction "1_1") (pintype "passive"))
      (node (ref "C59") (pin "1") (pinfunction "1_1") (pintype "passive"))
      (node (ref "C60") (pin "1") (pinfunction "1_1") (pintype "passive"))
      (node (ref "C61") (pin "1") (pinfunction "1_1") (pintype "passive"))
      (node (ref "D6") (pin "1") (pinfunction "K_1") (pintype "passive"))
      (node (ref "J7") (pin "3") (pinfunction "3_3") (pintype "passive"))
      (node (ref "J7") (pin "5") (pinfunction "5_5") (pintype "passive"))
      (node (ref "J7") (pin "9") (pinfunction "9_9") (pintype "passive"))
      (node (ref "Q1") (pin "2") (pinfunction "VSS_2") (pintype "passive"))
      (node (ref "U8") (pin "10") (pinfunction "GNDA+_10") (pintype "power_in"))
      (node (ref "U8") (pin "114") (pinfunction "VSS_114") (pintype "power_in"))
      (node (ref "U8") (pin "17") (pinfunction "VSS_17") (pintype "power_in"))
      (node (ref "U8") (pin "48") (pinfunction "VSS_48") (pintype "power_in"))
      (node (ref "U8") (pin "55") (pinfunction "VSS_55") (pintype "power_in"))
      (node (ref "U8") (pin "58") (pinfunction "VSS_58") (pintype "power_in"))
      (node (ref "U8") (pin "64") (pinfunction "~{WAKE}_64") (pintype "input"))
      (node (ref "U8") (pin "80") (pinfunction "VSS_80") (pintype "power_in"))
      (node (ref "U9") (pin "1") (pinfunction "GND_1") (pintype "passive"))
    )
    (net (code "84") (name "Net-(D6-A)") (class "Default")
      (node (ref "D6") (pin "2") (pinfunction "A_2") (pintype "passive"))
      (node (ref "R49") (pin "1") (pinfunction "1_1") (pintype "passive"))
    )
    (net (code "85") (name "unconnected-(J7-Pad7)") (class "Default")
      (node (ref "J7") (pin "7") (pinfunction "7_7") (pintype "passive+no_connect"))
    )
    (net (code "86") (name "unconnected-(U8-EN0RXIN-Pad53)") (class "Default")
      (node (ref "U8") (pin "53") (pinfunction "EN0RXIN_53") (pintype "bidirectional"))
    )
    (net (code "87") (name "unconnected-(U8-EN0RXIP-Pad54)") (class "Default")
      (node (ref "U8") (pin "54") (pinfunction "EN0RXIP_54") (pintype "bidirectional"))
    )
    (net (code "88") (name "unconnected-(U8-EN0TXON-Pad56)") (class "Default")
      (node (ref "U8") (pin "56") (pinfunction "EN0TXON_56") (pintype "bidirectional"))
    )
    (net (code "89") (name "unconnected-(U8-EN0TXOP-Pad57)") (class "Default")
      (node (ref "U8") (pin "57") (pinfunction "EN0TXOP_57") (pintype "bidirectional"))
    )
    (net (code "90") (name "unconnected-(U8-OSC1-Pad89)") (class "Default")
      (node (ref "U8") (pin "89") (pinfunction "OSC1_89") (pintype "output+no_connect"))
    )
    (net (code "91") (name "unconnected-(U8-PA5{slash}U3Tx-Pad38)") (class "Default")
      (node (ref "U8") (pin "38") (pinfunction "PA5/U3Tx_38") (pintype "bidirectional"))
    )
    (net (code "92") (name "unconnected-(U8-PB3{slash}EPI0S28-Pad92)") (class "Default")
      (node (ref "U8") (pin "92") (pinfunction "PB3/EPI0S28_92") (pintype "bidirectional"))
    )
    (net (code "93") (name "unconnected-(U8-PG0{slash}EPI0S11-Pad49)") (class "Default")
      (node (ref "U8") (pin "49") (pinfunction "PG0/EPI0S11_49") (pintype "bidirectional"))
    )
    (net (code "94") (name "unconnected-(U8-PG1{slash}EPI0S10-Pad50)") (class "Default")
      (node (ref "U8") (pin "50") (pinfunction "PG1/EPI0S10_50") (pintype "bidirectional"))
    )
    (net (code "95") (name "unconnected-(U8-PJ0{slash}U3Rx-Pad116)") (class "Default")
      (node (ref "U8") (pin "116") (pinfunction "PJ0/U3Rx_116") (pintype "bidirectional"))
    )
    (net (code "96") (name "unconnected-(U8-PJ1{slash}U3Tx-Pad117)") (class "Default")
      (node (ref "U8") (pin "117") (pinfunction "PJ1/U3Tx_117") (pintype "bidirectional"))
    )
    (net (code "97") (name "unconnected-(U8-PL0{slash}EPI0S16-Pad81)") (class "Default")
      (node (ref "U8") (pin "81") (pinfunction "PL0/EPI0S16_81") (pintype "bidirectional"))
    )
    (net (code "98") (name "unconnected-(U8-PL1{slash}EPI0S17-Pad82)") (class "Default")
      (node (ref "U8") (pin "82") (pinfunction "PL1/EPI0S17_82") (pintype "bidirectional"))
    )
    (net (code "99") (name "unconnected-(U8-PL2{slash}EPI0S18-Pad83)") (class "Default")
      (node (ref "U8") (pin "83") (pinfunction "PL2/EPI0S18_83") (pintype "bidirectional"))
    )
    (net (code "100") (name "unconnected-(U8-PL3{slash}EPI0S19-Pad84)") (class "Default")
      (node (ref "U8") (pin "84") (pinfunction "PL3/EPI0S19_84") (pintype "bidirectional"))
    )
    (net (code "101") (name "unconnected-(U8-PL4{slash}EPI0S26-Pad85)") (class "Default")
      (node (ref "U8") (pin "85") (pinfunction "PL4/EPI0S26_85") (pintype "bidirectional"))
    )
    (net (code "102") (name "unconnected-(U8-PL5{slash}EPI0S33-Pad86)") (class "Default")
      (node (ref "U8") (pin "86") (pinfunction "PL5/EPI0S33_86") (pintype "bidirectional"))
    )
    (net (code "103") (name "unconnected-(U8-PM0{slash}EPI0S15-Pad78)") (class "Default")
      (node (ref "U8") (pin "78") (pinfunction "PM0/EPI0S15_78") (pintype "bidirectional"))
    )
    (net (code "104") (name "unconnected-(U8-PM1{slash}EPI0S14-Pad77)") (class "Default")
      (node (ref "U8") (pin "77") (pinfunction "PM1/EPI0S14_77") (pintype "bidirectional"))
    )
    (net (code "105") (name "unconnected-(U8-PM2{slash}EPI0S13-Pad76)") (class "Default")
      (node (ref "U8") (pin "76") (pinfunction "PM2/EPI0S13_76") (pintype "bidirectional"))
    )
    (net (code "106") (name "unconnected-(U8-PM3{slash}EPI0S12-Pad75)") (class "Default")
      (node (ref "U8") (pin "75") (pinfunction "PM3/EPI0S12_75") (pintype "bidirectional"))
    )
    (net (code "107") (name "unconnected-(U8-PM4-Pad74)") (class "Default")
      (node (ref "U8") (pin "74") (pinfunction "PM4_74") (pintype "bidirectional"))
    )
    (net (code "108") (name "unconnected-(U8-PM5-Pad73)") (class "Default")
      (node (ref "U8") (pin "73") (pinfunction "PM5_73") (pintype "bidirectional"))
    )
    (net (code "109") (name "unconnected-(U8-PM6-Pad72)") (class "Default")
      (node (ref "U8") (pin "72") (pinfunction "PM6_72") (pintype "bidirectional"))
    )
    (net (code "110") (name "unconnected-(U8-PM7-Pad71)") (class "Default")
      (node (ref "U8") (pin "71") (pinfunction "PM7_71") (pintype "bidirectional"))
    )
    (net (code "111") (name "unconnected-(U8-PN2{slash}EPI0S29-Pad109)") (class "Default")
      (node (ref "U8") (pin "109") (pinfunction "PN2/EPI0S29_109") (pintype "bidirectional"))
    )
    (net (code "112") (name "unconnected-(U8-PN3{slash}EPI0S30-Pad110)") (class "Default")
      (node (ref "U8") (pin "110") (pinfunction "PN3/EPI0S30_110") (pintype "bidirectional"))
    )
    (net (code "113") (name "unconnected-(U8-PN4{slash}EPI0S34-Pad111)") (class "Default")
      (node (ref "U8") (pin "111") (pinfunction "PN4/EPI0S34_111") (pintype "bidirectional"))
    )
    (net (code "114") (name "unconnected-(U8-PN5{slash}EPI0S35-Pad112)") (class "Default")
      (node (ref "U8") (pin "112") (pinfunction "PN5/EPI0S35_112") (pintype "bidirectional"))
    )
    (net (code "115") (name "unconnected-(U8-PP0{slash}U6Rx-Pad118)") (class "Default")
      (node (ref "U8") (pin "118") (pinfunction "PP0/U6Rx_118") (pintype "bidirectional"))
    )
    (net (code "116") (name "unconnected-(U8-PP1{slash}U6Tx-Pad119)") (class "Default")
      (node (ref "U8") (pin "119") (pinfunction "PP1/U6Tx_119") (pintype "bidirectional"))
    )
    (net (code "117") (name "unconnected-(U8-PQ0{slash}EPI0S20-Pad5)") (class "Default")
      (node (ref "U8") (pin "5") (pinfunction "PQ0/EPI0S20_5") (pintype "bidirectional"))
    )
    (net (code "118") (name "unconnected-(U8-PQ1{slash}EPI0S21-Pad6)") (class "Default")
      (node (ref "U8") (pin "6") (pinfunction "PQ1/EPI0S21_6") (pintype "bidirectional"))
    )
    (net (code "119") (name "unconnected-(U8-PQ2{slash}EPI0S22-Pad11)") (class "Default")
      (node (ref "U8") (pin "11") (pinfunction "PQ2/EPI0S22_11") (pintype "bidirectional"))
    )
    (net (code "120") (name "unconnected-(U8-PQ4{slash}U1Rx-Pad102)") (class "Default")
      (node (ref "U8") (pin "102") (pinfunction "PQ4/U1Rx_102") (pintype "bidirectional"))
    )
    (net (code "121") (name "unconnected-(U8-RBIAS-Pad59)") (class "Default")
      (node (ref "U8") (pin "59") (pinfunction "RBIAS_59") (pintype "output+no_connect"))
    )
    (net (code "122") (name "unconnected-(U8-VBAT-Pad68)") (class "Default")
      (node (ref "U8") (pin "68") (pinfunction "VBAT_68") (pintype "power_in"))
    )
    (net (code "123") (name "unconnected-(U8-XOSC0-Pad66)") (class "Default")
      (node (ref "U8") (pin "66") (pinfunction "XOSC0_66") (pintype "input+no_connect"))
    )
    (net (code "124") (name "unconnected-(U8-XOSC1-Pad67)") (class "Default")
      (node (ref "U8") (pin "67") (pinfunction "XOSC1_67") (pintype "output+no_connect"))
    )
    (net (code "125") (name "unconnected-(U8-~{HIB}-Pad65)") (class "Default")
      (node (ref "U8") (pin "65") (pinfunction "~{HIB}_65") (pintype "output+no_connect"))
    )
  )
)
